# Industrial_project_work_circuits.net
KiCad netlist of a schematic drawn in EasyEDA
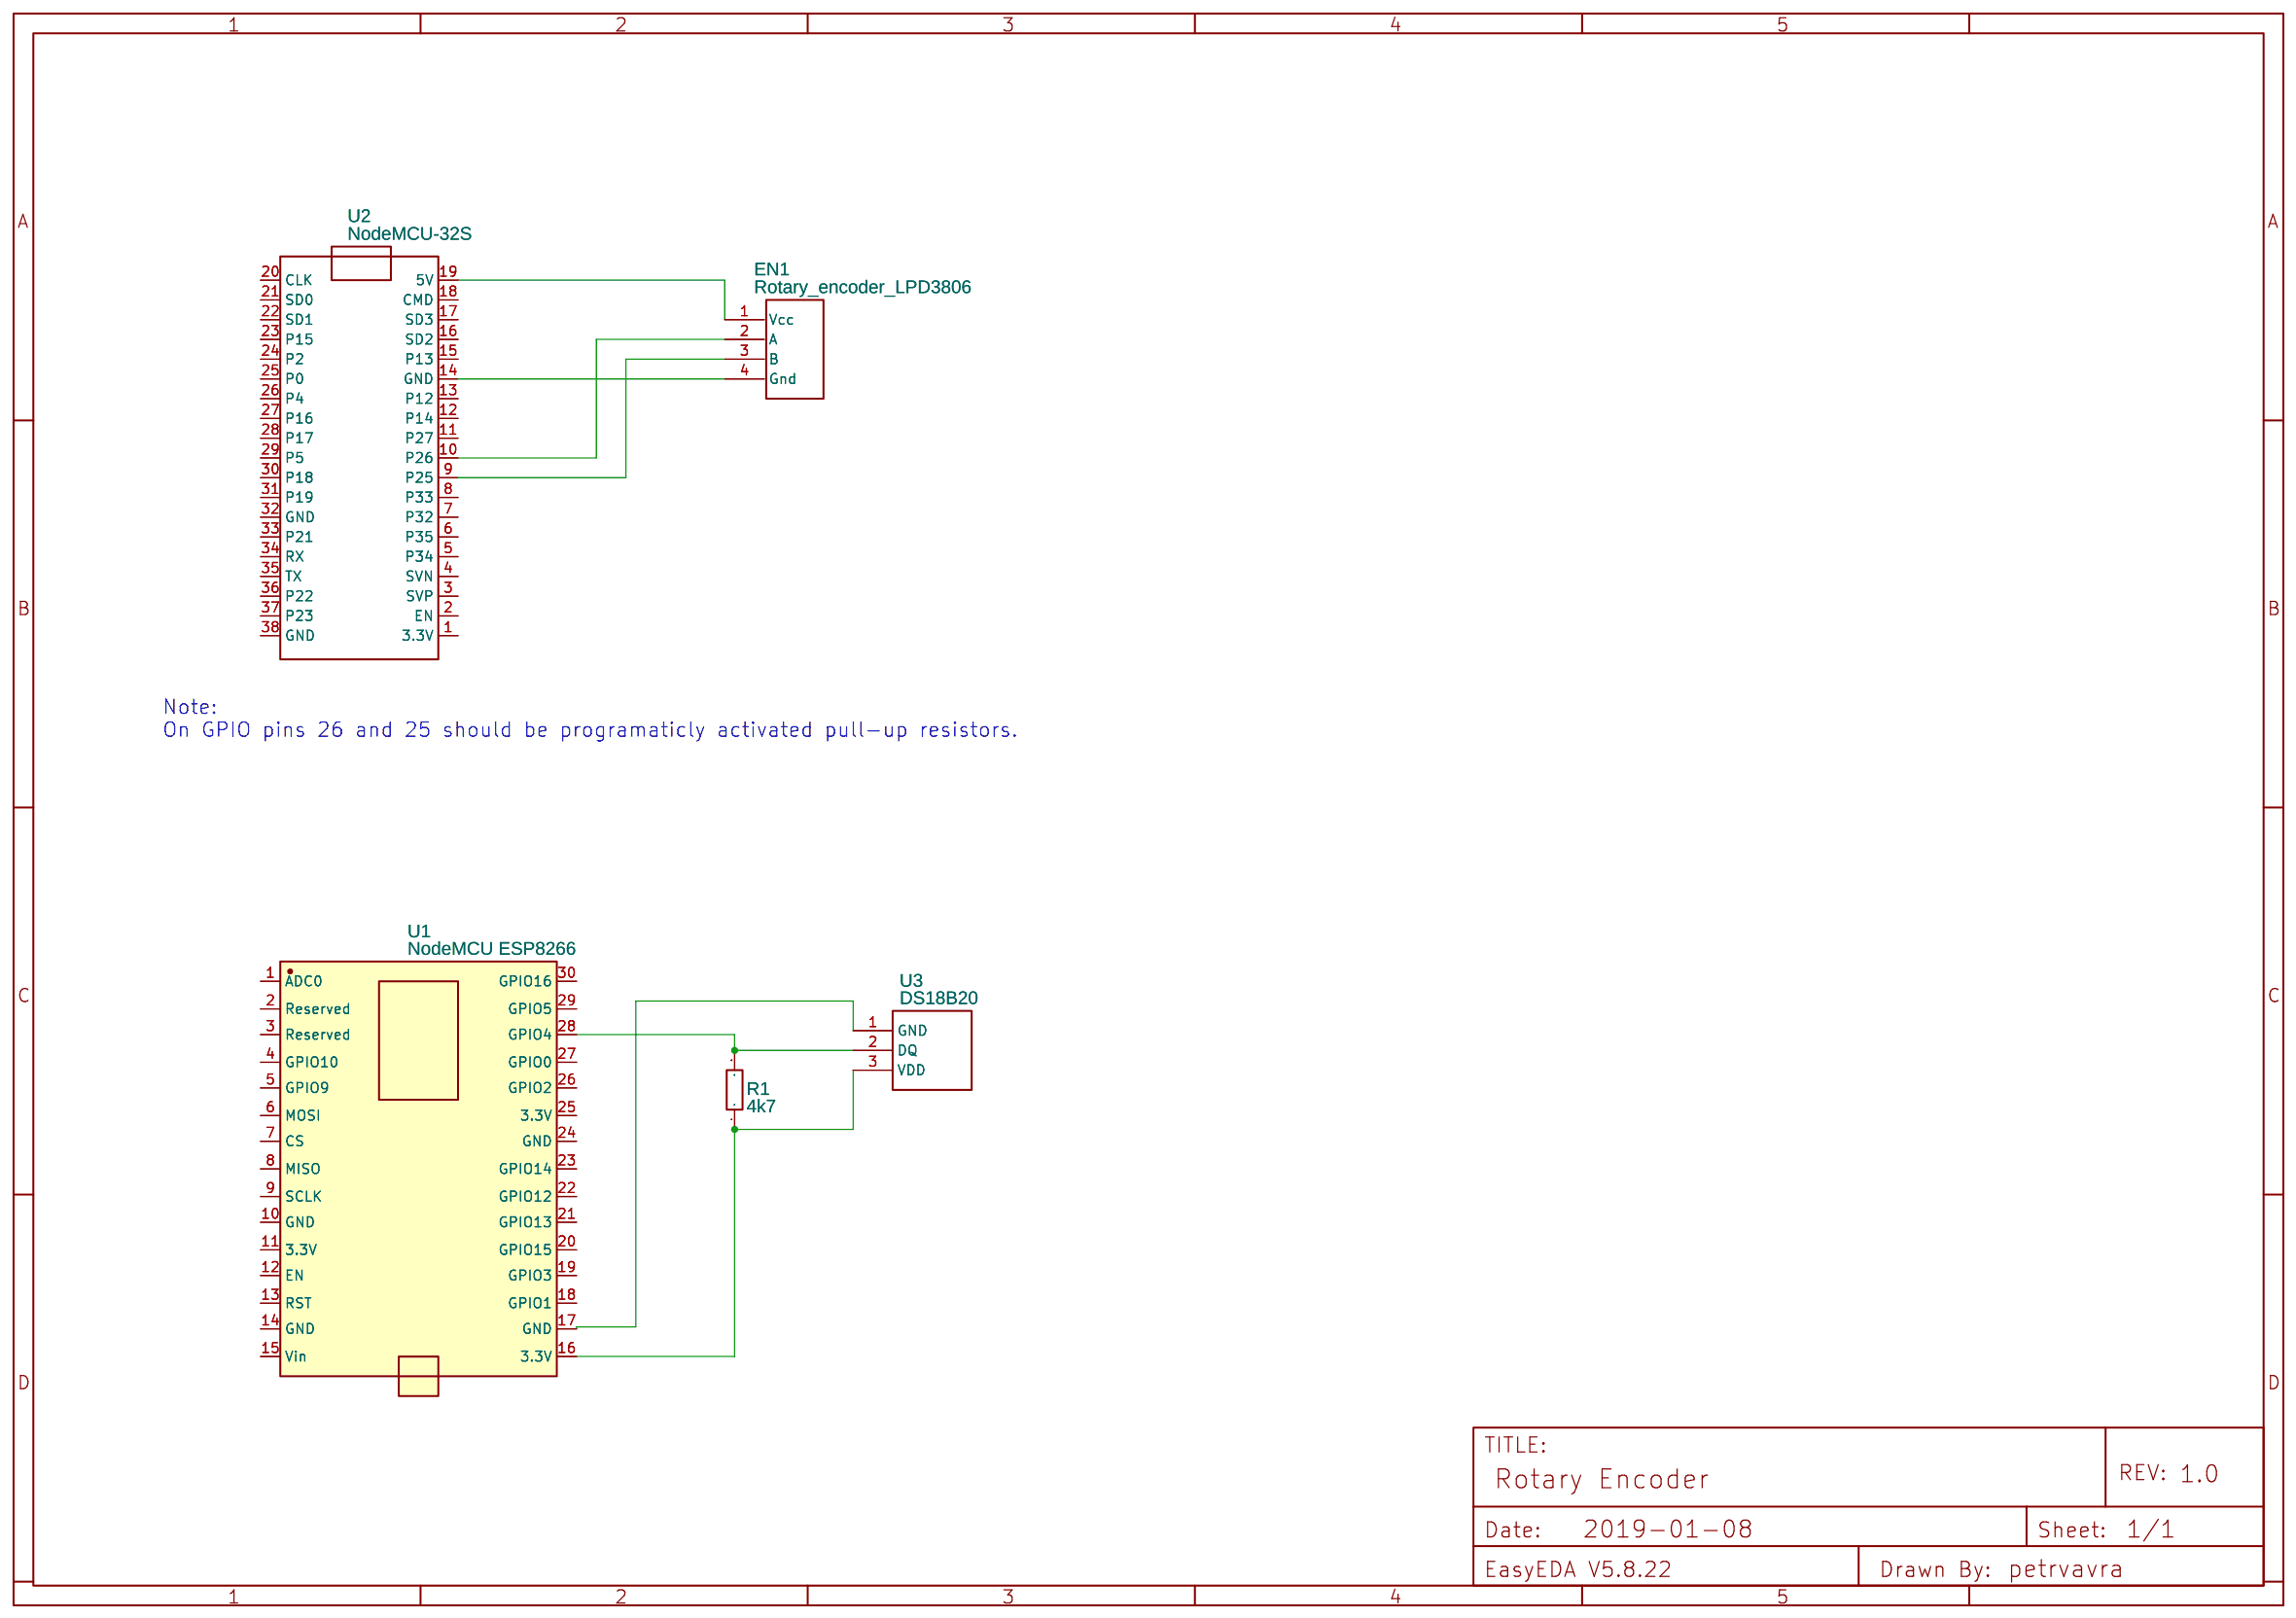
[diagram p0: schematic sheet]

(export (version "E")
  (design (tool "Eeschema 10.0.6"))
  (components
    (comp (ref "EN1")
      (value "Rotary_encoder_LPD3806")
      (fields (field (name "BOM_Supplier Part") "LPD3806"))
      (libsource (lib "") (part "Unknown_400_175"))
    )
    (comp (ref "R1")
      (value "4k7")
      (fields (field (name "BOM_Manufacturer Part") "?"))
      (libsource (lib "") (part "Res_AXIAL-0.6(1W)_EU"))
    )
    (comp (ref "U1")
      (value "NodeMCU ESP8266")
      (fields (field (name "BOM_Manufacturer Part") "New SchematicLib"))
      (libsource (lib "") (part "Unknown_135_480"))
    )
    (comp (ref "U2")
      (value "NodeMCU-32S")
      (fields (field (name "BOM_Manufacturer Part") "?"))
      (libsource (lib "") (part "Unknown_175_325"))
    )
    (comp (ref "U3")
      (value "DS18B20")
      (fields (field (name "BOM_Manufacturer Part") "DS18B20+") (field (name "BOM_Supplier Part") "C9753"))
      (libsource (lib "") (part "Unknown_465_535"))
    )
  )
  (nets
    (net (code "1") (name "Net-(EN1-A)") (class "Default")
      (node (ref "EN1") (pin "2") (pinfunction "A_2") (pintype "unspecified"))
      (node (ref "U2") (pin "10") (pinfunction "P26_10") (pintype "unspecified"))
    )
    (net (code "2") (name "Net-(EN1-B)") (class "Default")
      (node (ref "EN1") (pin "3") (pinfunction "B_3") (pintype "unspecified"))
      (node (ref "U2") (pin "9") (pinfunction "P25_9") (pintype "unspecified"))
    )
    (net (code "3") (name "Net-(EN1-Gnd)") (class "Default")
      (node (ref "EN1") (pin "4") (pinfunction "Gnd_4") (pintype "unspecified"))
      (node (ref "U2") (pin "14") (pinfunction "GND_14") (pintype "unspecified"))
    )
    (net (code "4") (name "Net-(EN1-Vcc)") (class "Default")
      (node (ref "EN1") (pin "1") (pinfunction "Vcc_1") (pintype "unspecified"))
      (node (ref "U2") (pin "19") (pinfunction "5V_19") (pintype "unspecified"))
    )
    (net (code "5") (name "Net-(U1-GPIO4)") (class "Default")
      (node (ref "R1") (pin "2") (pinfunction "2_2") (pintype "unspecified"))
      (node (ref "U1") (pin "28") (pinfunction "GPIO4_28") (pintype "unspecified"))
      (node (ref "U3") (pin "2") (pinfunction "DQ_2") (pintype "unspecified"))
    )
    (net (code "6") (name "Net-(U3-GND)") (class "Default")
      (node (ref "U1") (pin "17") (pinfunction "GND_17") (pintype "unspecified"))
      (node (ref "U3") (pin "1") (pinfunction "GND_1") (pintype "unspecified"))
    )
    (net (code "7") (name "Net-(U3-VDD)") (class "Default")
      (node (ref "R1") (pin "1") (pinfunction "1_1") (pintype "unspecified"))
      (node (ref "U1") (pin "16") (pinfunction "3.3V_16") (pintype "unspecified"))
      (node (ref "U3") (pin "3") (pinfunction "VDD_3") (pintype "unspecified"))
    )
    (net (code "8") (name "unconnected-(U1-3.3V-Pad11)") (class "Default")
      (node (ref "U1") (pin "11") (pinfunction "3.3V_11") (pintype "unspecified"))
    )
    (net (code "9") (name "unconnected-(U1-3.3V-Pad25)") (class "Default")
      (node (ref "U1") (pin "25") (pinfunction "3.3V_25") (pintype "unspecified"))
    )
    (net (code "10") (name "unconnected-(U1-ADC0-Pad1)") (class "Default")
      (node (ref "U1") (pin "1") (pinfunction "ADC0_1") (pintype "unspecified"))
    )
    (net (code "11") (name "unconnected-(U1-CS-Pad7)") (class "Default")
      (node (ref "U1") (pin "7") (pinfunction "CS_7") (pintype "unspecified"))
    )
    (net (code "12") (name "unconnected-(U1-EN-Pad12)") (class "Default")
      (node (ref "U1") (pin "12") (pinfunction "EN_12") (pintype "unspecified"))
    )
    (net (code "13") (name "unconnected-(U1-GND-Pad10)") (class "Default")
      (node (ref "U1") (pin "10") (pinfunction "GND_10") (pintype "unspecified"))
    )
    (net (code "14") (name "unconnected-(U1-GND-Pad14)") (class "Default")
      (node (ref "U1") (pin "14") (pinfunction "GND_14") (pintype "unspecified"))
    )
    (net (code "15") (name "unconnected-(U1-GND-Pad24)") (class "Default")
      (node (ref "U1") (pin "24") (pinfunction "GND_24") (pintype "unspecified"))
    )
    (net (code "16") (name "unconnected-(U1-GPIO0-Pad27)") (class "Default")
      (node (ref "U1") (pin "27") (pinfunction "GPIO0_27") (pintype "unspecified"))
    )
    (net (code "17") (name "unconnected-(U1-GPIO1-Pad18)") (class "Default")
      (node (ref "U1") (pin "18") (pinfunction "GPIO1_18") (pintype "unspecified"))
    )
    (net (code "18") (name "unconnected-(U1-GPIO2-Pad26)") (class "Default")
      (node (ref "U1") (pin "26") (pinfunction "GPIO2_26") (pintype "unspecified"))
    )
    (net (code "19") (name "unconnected-(U1-GPIO3-Pad19)") (class "Default")
      (node (ref "U1") (pin "19") (pinfunction "GPIO3_19") (pintype "unspecified"))
    )
    (net (code "20") (name "unconnected-(U1-GPIO5-Pad29)") (class "Default")
      (node (ref "U1") (pin "29") (pinfunction "GPIO5_29") (pintype "unspecified"))
    )
    (net (code "21") (name "unconnected-(U1-GPIO9-Pad5)") (class "Default")
      (node (ref "U1") (pin "5") (pinfunction "GPIO9_5") (pintype "unspecified"))
    )
    (net (code "22") (name "unconnected-(U1-GPIO10-Pad4)") (class "Default")
      (node (ref "U1") (pin "4") (pinfunction "GPIO10_4") (pintype "unspecified"))
    )
    (net (code "23") (name "unconnected-(U1-GPIO12-Pad22)") (class "Default")
      (node (ref "U1") (pin "22") (pinfunction "GPIO12_22") (pintype "unspecified"))
    )
    (net (code "24") (name "unconnected-(U1-GPIO13-Pad21)") (class "Default")
      (node (ref "U1") (pin "21") (pinfunction "GPIO13_21") (pintype "unspecified"))
    )
    (net (code "25") (name "unconnected-(U1-GPIO14-Pad23)") (class "Default")
      (node (ref "U1") (pin "23") (pinfunction "GPIO14_23") (pintype "unspecified"))
    )
    (net (code "26") (name "unconnected-(U1-GPIO15-Pad20)") (class "Default")
      (node (ref "U1") (pin "20") (pinfunction "GPIO15_20") (pintype "unspecified"))
    )
    (net (code "27") (name "unconnected-(U1-GPIO16-Pad30)") (class "Default")
      (node (ref "U1") (pin "30") (pinfunction "GPIO16_30") (pintype "unspecified"))
    )
    (net (code "28") (name "unconnected-(U1-MISO-Pad8)") (class "Default")
      (node (ref "U1") (pin "8") (pinfunction "MISO_8") (pintype "unspecified"))
    )
    (net (code "29") (name "unconnected-(U1-MOSI-Pad6)") (class "Default")
      (node (ref "U1") (pin "6") (pinfunction "MOSI_6") (pintype "unspecified"))
    )
    (net (code "30") (name "unconnected-(U1-RST-Pad13)") (class "Default")
      (node (ref "U1") (pin "13") (pinfunction "RST_13") (pintype "unspecified"))
    )
    (net (code "31") (name "unconnected-(U1-Reserved-Pad2)") (class "Default")
      (node (ref "U1") (pin "2") (pinfunction "Reserved_2") (pintype "unspecified"))
    )
    (net (code "32") (name "unconnected-(U1-Reserved-Pad3)") (class "Default")
      (node (ref "U1") (pin "3") (pinfunction "Reserved_3") (pintype "unspecified"))
    )
    (net (code "33") (name "unconnected-(U1-SCLK-Pad9)") (class "Default")
      (node (ref "U1") (pin "9") (pinfunction "SCLK_9") (pintype "unspecified"))
    )
    (net (code "34") (name "unconnected-(U1-Vin-Pad15)") (class "Default")
      (node (ref "U1") (pin "15") (pinfunction "Vin_15") (pintype "unspecified"))
    )
    (net (code "35") (name "unconnected-(U2-3.3V-Pad1)") (class "Default")
      (node (ref "U2") (pin "1") (pinfunction "3.3V_1") (pintype "passive"))
    )
    (net (code "36") (name "unconnected-(U2-CLK-Pad20)") (class "Default")
      (node (ref "U2") (pin "20") (pinfunction "CLK_20") (pintype "unspecified"))
    )
    (net (code "37") (name "unconnected-(U2-CMD-Pad18)") (class "Default")
      (node (ref "U2") (pin "18") (pinfunction "CMD_18") (pintype "unspecified"))
    )
    (net (code "38") (name "unconnected-(U2-EN-Pad2)") (class "Default")
      (node (ref "U2") (pin "2") (pinfunction "EN_2") (pintype "unspecified"))
    )
    (net (code "39") (name "unconnected-(U2-GND-Pad32)") (class "Default")
      (node (ref "U2") (pin "32") (pinfunction "GND_32") (pintype "unspecified"))
    )
    (net (code "40") (name "unconnected-(U2-GND-Pad38)") (class "Default")
      (node (ref "U2") (pin "38") (pinfunction "GND_38") (pintype "unspecified"))
    )
    (net (code "41") (name "unconnected-(U2-P0-Pad25)") (class "Default")
      (node (ref "U2") (pin "25") (pinfunction "P0_25") (pintype "unspecified"))
    )
    (net (code "42") (name "unconnected-(U2-P2-Pad24)") (class "Default")
      (node (ref "U2") (pin "24") (pinfunction "P2_24") (pintype "unspecified"))
    )
    (net (code "43") (name "unconnected-(U2-P4-Pad26)") (class "Default")
      (node (ref "U2") (pin "26") (pinfunction "P4_26") (pintype "unspecified"))
    )
    (net (code "44") (name "unconnected-(U2-P5-Pad29)") (class "Default")
      (node (ref "U2") (pin "29") (pinfunction "P5_29") (pintype "unspecified"))
    )
    (net (code "45") (name "unconnected-(U2-P12-Pad13)") (class "Default")
      (node (ref "U2") (pin "13") (pinfunction "P12_13") (pintype "unspecified"))
    )
    (net (code "46") (name "unconnected-(U2-P13-Pad15)") (class "Default")
      (node (ref "U2") (pin "15") (pinfunction "P13_15") (pintype "unspecified"))
    )
    (net (code "47") (name "unconnected-(U2-P14-Pad12)") (class "Default")
      (node (ref "U2") (pin "12") (pinfunction "P14_12") (pintype "unspecified"))
    )
    (net (code "48") (name "unconnected-(U2-P15-Pad23)") (class "Default")
      (node (ref "U2") (pin "23") (pinfunction "P15_23") (pintype "unspecified"))
    )
    (net (code "49") (name "unconnected-(U2-P16-Pad27)") (class "Default")
      (node (ref "U2") (pin "27") (pinfunction "P16_27") (pintype "unspecified"))
    )
    (net (code "50") (name "unconnected-(U2-P17-Pad28)") (class "Default")
      (node (ref "U2") (pin "28") (pinfunction "P17_28") (pintype "unspecified"))
    )
    (net (code "51") (name "unconnected-(U2-P18-Pad30)") (class "Default")
      (node (ref "U2") (pin "30") (pinfunction "P18_30") (pintype "unspecified"))
    )
    (net (code "52") (name "unconnected-(U2-P19-Pad31)") (class "Default")
      (node (ref "U2") (pin "31") (pinfunction "P19_31") (pintype "unspecified"))
    )
    (net (code "53") (name "unconnected-(U2-P21-Pad33)") (class "Default")
      (node (ref "U2") (pin "33") (pinfunction "P21_33") (pintype "unspecified"))
    )
    (net (code "54") (name "unconnected-(U2-P22-Pad36)") (class "Default")
      (node (ref "U2") (pin "36") (pinfunction "P22_36") (pintype "unspecified"))
    )
    (net (code "55") (name "unconnected-(U2-P23-Pad37)") (class "Default")
      (node (ref "U2") (pin "37") (pinfunction "P23_37") (pintype "unspecified"))
    )
    (net (code "56") (name "unconnected-(U2-P27-Pad11)") (class "Default")
      (node (ref "U2") (pin "11") (pinfunction "P27_11") (pintype "unspecified"))
    )
    (net (code "57") (name "unconnected-(U2-P32-Pad7)") (class "Default")
      (node (ref "U2") (pin "7") (pinfunction "P32_7") (pintype "unspecified"))
    )
    (net (code "58") (name "unconnected-(U2-P33-Pad8)") (class "Default")
      (node (ref "U2") (pin "8") (pinfunction "P33_8") (pintype "unspecified"))
    )
    (net (code "59") (name "unconnected-(U2-P34-Pad5)") (class "Default")
      (node (ref "U2") (pin "5") (pinfunction "P34_5") (pintype "unspecified"))
    )
    (net (code "60") (name "unconnected-(U2-P35-Pad6)") (class "Default")
      (node (ref "U2") (pin "6") (pinfunction "P35_6") (pintype "unspecified"))
    )
    (net (code "61") (name "unconnected-(U2-RX-Pad34)") (class "Default")
      (node (ref "U2") (pin "34") (pinfunction "RX_34") (pintype "unspecified"))
    )
    (net (code "62") (name "unconnected-(U2-SD0-Pad21)") (class "Default")
      (node (ref "U2") (pin "21") (pinfunction "SD0_21") (pintype "unspecified"))
    )
    (net (code "63") (name "unconnected-(U2-SD1-Pad22)") (class "Default")
      (node (ref "U2") (pin "22") (pinfunction "SD1_22") (pintype "unspecified"))
    )
    (net (code "64") (name "unconnected-(U2-SD2-Pad16)") (class "Default")
      (node (ref "U2") (pin "16") (pinfunction "SD2_16") (pintype "unspecified"))
    )
    (net (code "65") (name "unconnected-(U2-SD3-Pad17)") (class "Default")
      (node (ref "U2") (pin "17") (pinfunction "SD3_17") (pintype "unspecified"))
    )
    (net (code "66") (name "unconnected-(U2-SVN-Pad4)") (class "Default")
      (node (ref "U2") (pin "4") (pinfunction "SVN_4") (pintype "unspecified"))
    )
    (net (code "67") (name "unconnected-(U2-SVP-Pad3)") (class "Default")
      (node (ref "U2") (pin "3") (pinfunction "SVP_3") (pintype "unspecified"))
    )
    (net (code "68") (name "unconnected-(U2-TX-Pad35)") (class "Default")
      (node (ref "U2") (pin "35") (pinfunction "TX_35") (pintype "unspecified"))
    )
  )
)
